# SynchronousBuck.net
KiCad netlist of a schematic drawn in Altium Designer
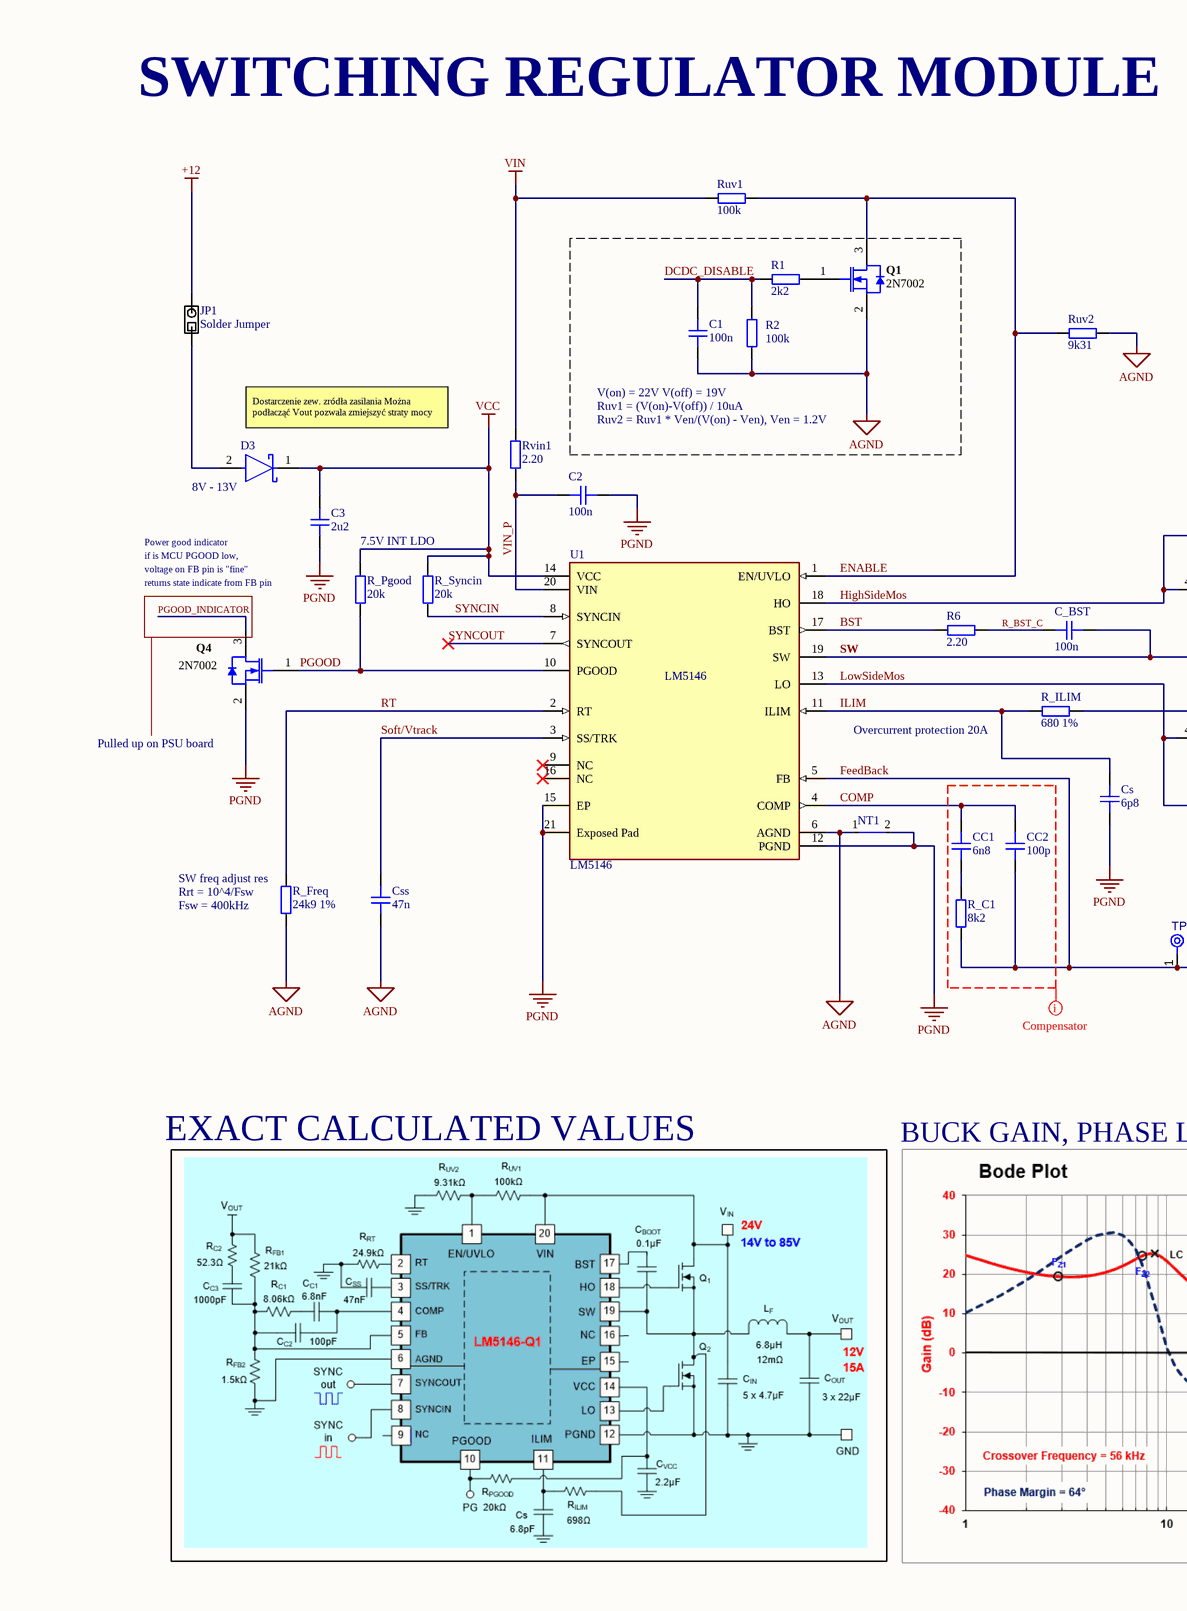
[diagram p0: SynchronousBuck.SchDoc, middle]
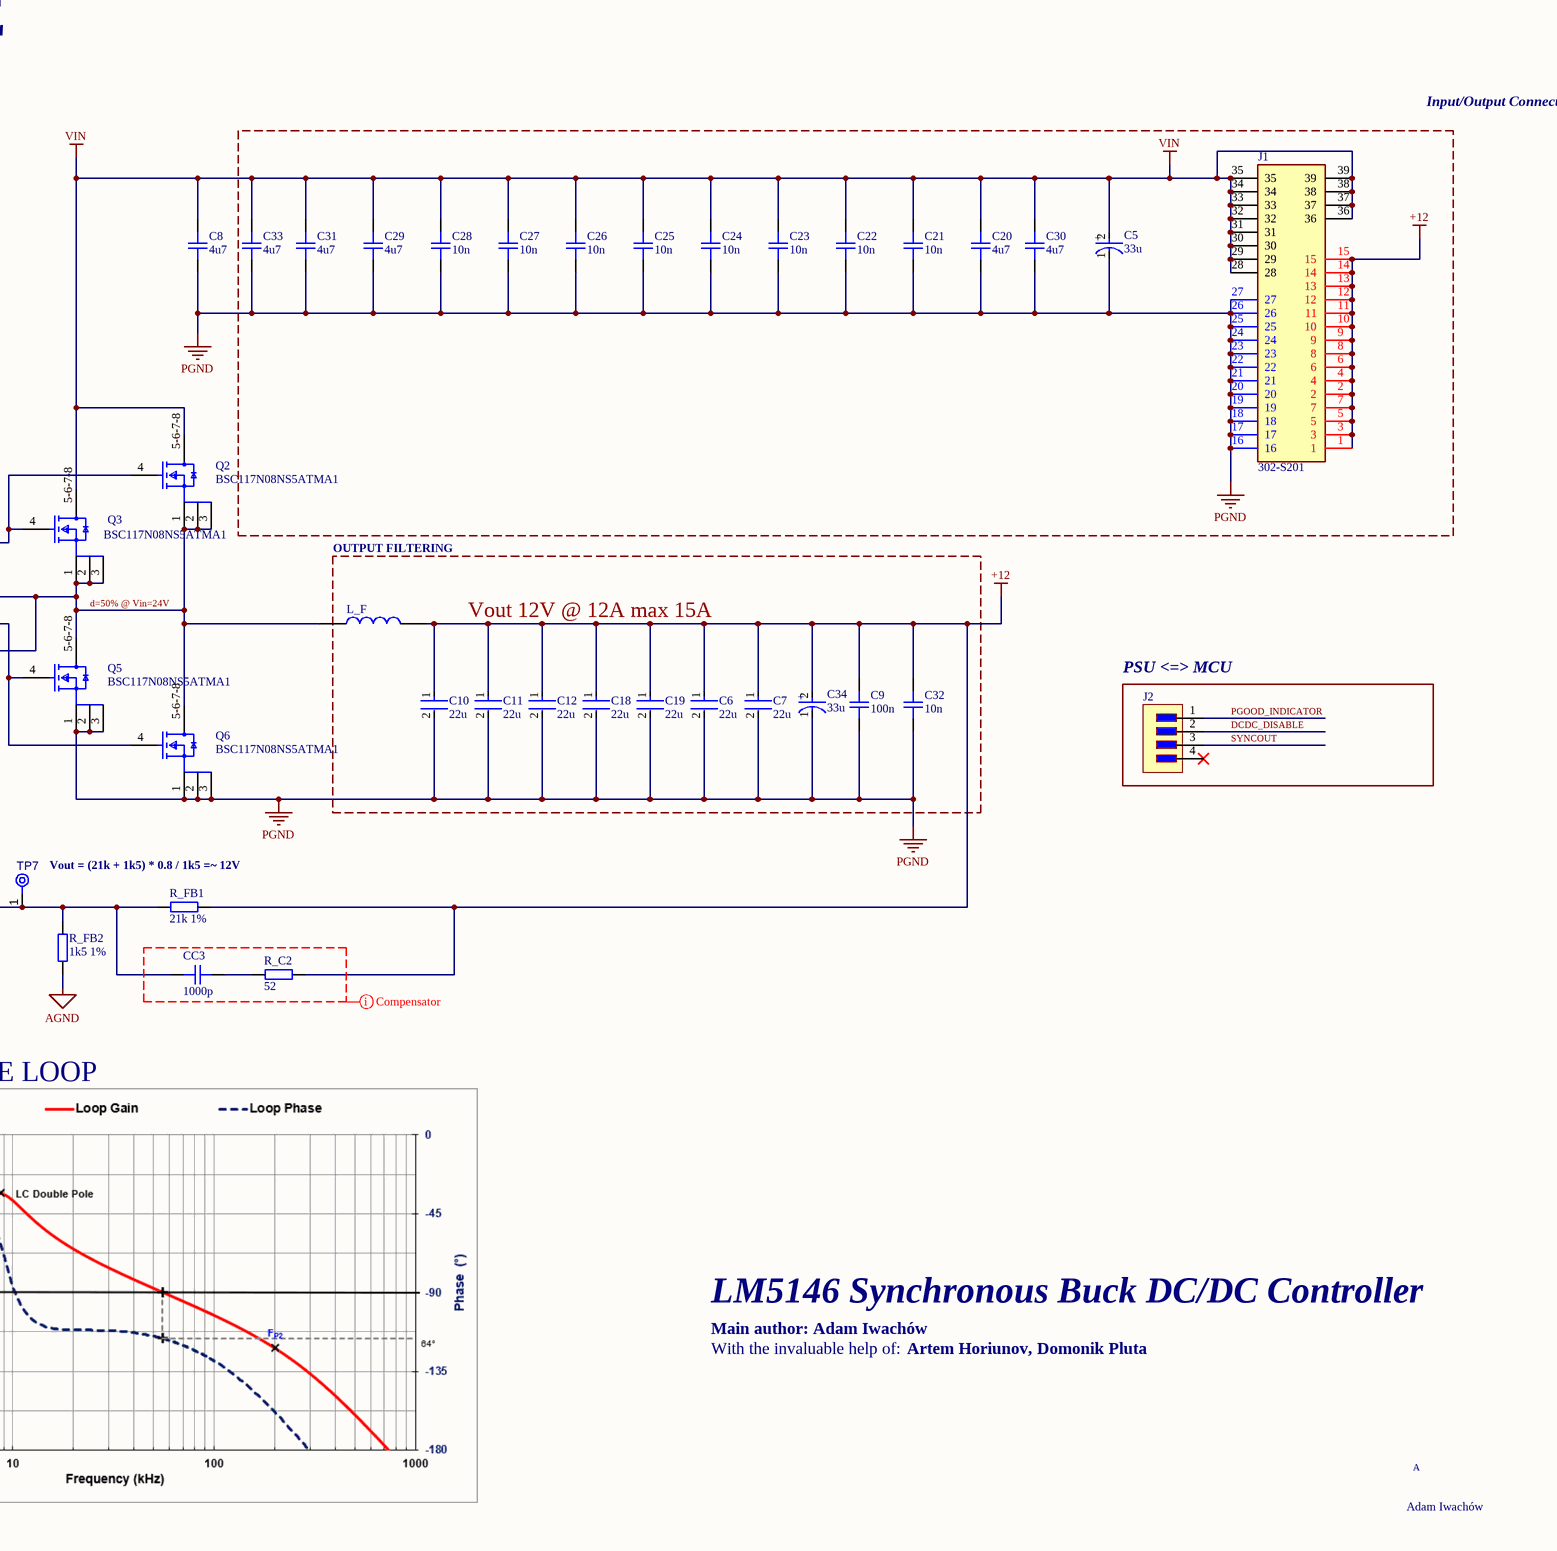
[diagram p1: SynchronousBuck.SchDoc, right]

(export (version "E")
  (design (tool "Eeschema 10.0.6"))
  (components
    (comp (ref "C1")
      (value "100n")
      (footprint "CAP_0603")
      (description "Capacitor SMD 0603")
      (libsource (lib "Schematic-Lib-PhilsLab") (part "CAP_0603"))
    )
    (comp (ref "C2")
      (value "100n")
      (footprint "CAP_0603")
      (description "Capacitor SMD 0603")
      (libsource (lib "Schematic-Lib-PhilsLab") (part "CAP_0603"))
    )
    (comp (ref "C3")
      (value "2u2")
      (footprint "CAP_0603")
      (description "Capacitor SMD 0603")
      (libsource (lib "Schematic-Lib-PhilsLab") (part "CAP_0603"))
    )
    (comp (ref "C5")
      (value "33u")
      (footprint "FP-FKG-MFG")
      (description "CAP ALUM 220UF 20% 50V SMD EEE-FK1H221GP")
      (fields (field (name "VOLTAGE") "50V") (field (name "TOLERANCE") "20%"))
      (libsource (lib "Altium Content Vault") (part "a00bbbee19879c290e62620ae7e47b1"))
    )
    (comp (ref "C6")
      (value "22u")
      (footprint "FP-GRM32E-0_3-0_2-MFG")
      (fields (field (name "VOLTAGE") "25V") (field (name "TOLERANCE") "10%"))
      (libsource (lib "Altium Content Vault") (part "02cd4be3c70576c341d710602a673aa"))
    )
    (comp (ref "C7")
      (value "22u")
      (footprint "FP-GRM32E-0_3-0_2-MFG")
      (fields (field (name "VOLTAGE") "25V") (field (name "TOLERANCE") "10%"))
      (libsource (lib "Altium Content Vault") (part "02cd4be3c70576c341d710602a673aa"))
    )
    (comp (ref "C8")
      (value "4u7")
      (footprint "CAP_1210")
      (description "Capacitor SMD 1210")
      (libsource (lib "Schematic-Lib-PhilsLab") (part "CAP_1210"))
    )
    (comp (ref "C9")
      (value "100n")
      (footprint "CAP_0603")
      (description "Capacitor SMD 0603")
      (libsource (lib "Schematic-Lib-PhilsLab") (part "CAP_0603"))
    )
    (comp (ref "C10")
      (value "22u")
      (footprint "FP-GRM32E-0_3-0_2-MFG")
      (fields (field (name "VOLTAGE") "25V") (field (name "TOLERANCE") "10%"))
      (libsource (lib "Altium Content Vault") (part "02cd4be3c70576c341d710602a673aa"))
    )
    (comp (ref "C11")
      (value "22u")
      (footprint "FP-GRM32E-0_3-0_2-MFG")
      (fields (field (name "VOLTAGE") "25V") (field (name "TOLERANCE") "10%"))
      (libsource (lib "Altium Content Vault") (part "02cd4be3c70576c341d710602a673aa"))
    )
    (comp (ref "C12")
      (value "22u")
      (footprint "FP-GRM32E-0_3-0_2-MFG")
      (fields (field (name "VOLTAGE") "25V") (field (name "TOLERANCE") "10%"))
      (libsource (lib "Altium Content Vault") (part "02cd4be3c70576c341d710602a673aa"))
    )
    (comp (ref "C18")
      (value "22u")
      (footprint "FP-GRM32E-0_3-0_2-MFG")
      (fields (field (name "VOLTAGE") "25V") (field (name "TOLERANCE") "10%"))
      (libsource (lib "Altium Content Vault") (part "02cd4be3c70576c341d710602a673aa"))
    )
    (comp (ref "C19")
      (value "22u")
      (footprint "FP-GRM32E-0_3-0_2-MFG")
      (fields (field (name "VOLTAGE") "25V") (field (name "TOLERANCE") "10%"))
      (libsource (lib "Altium Content Vault") (part "02cd4be3c70576c341d710602a673aa"))
    )
    (comp (ref "C20")
      (value "4u7")
      (footprint "CAP_1210")
      (description "Capacitor SMD 1210")
      (libsource (lib "Schematic-Lib-PhilsLab") (part "CAP_1210"))
    )
    (comp (ref "C21")
      (value "10n")
      (footprint "CAP_0603")
      (description "Capacitor SMD 0603")
      (libsource (lib "Schematic-Lib-PhilsLab") (part "CAP_0603"))
    )
    (comp (ref "C22")
      (value "10n")
      (footprint "CAP_0603")
      (description "Capacitor SMD 0603")
      (libsource (lib "Schematic-Lib-PhilsLab") (part "CAP_0603"))
    )
    (comp (ref "C23")
      (value "10n")
      (footprint "CAP_0603")
      (description "Capacitor SMD 0603")
      (libsource (lib "Schematic-Lib-PhilsLab") (part "CAP_0603"))
    )
    (comp (ref "C24")
      (value "10n")
      (footprint "CAP_0603")
      (description "Capacitor SMD 0603 GRM188R71H103KA01D")
      (libsource (lib "Schematic-Lib-PhilsLab") (part "CAP_0603"))
    )
    (comp (ref "C25")
      (value "10n")
      (footprint "CAP_0603")
      (description "Capacitor SMD 0603")
      (libsource (lib "Schematic-Lib-PhilsLab") (part "CAP_0603"))
    )
    (comp (ref "C26")
      (value "10n")
      (footprint "CAP_0603")
      (description "Capacitor SMD 0603")
      (libsource (lib "Schematic-Lib-PhilsLab") (part "CAP_0603"))
    )
    (comp (ref "C27")
      (value "10n")
      (footprint "CAP_0603")
      (description "Capacitor SMD 0603")
      (libsource (lib "Schematic-Lib-PhilsLab") (part "CAP_0603"))
    )
    (comp (ref "C28")
      (value "10n")
      (footprint "CAP_0603")
      (description "Capacitor SMD 0603")
      (libsource (lib "Schematic-Lib-PhilsLab") (part "CAP_0603"))
    )
    (comp (ref "C29")
      (value "4u7")
      (footprint "CAP_1210")
      (description "Capacitor SMD 1210")
      (libsource (lib "Schematic-Lib-PhilsLab") (part "CAP_1210"))
    )
    (comp (ref "C30")
      (value "4u7")
      (footprint "CAP_1210")
      (description "Capacitor SMD 1210")
      (libsource (lib "Schematic-Lib-PhilsLab") (part "CAP_1210"))
    )
    (comp (ref "C31")
      (value "4u7")
      (footprint "CAP_1210")
      (description "Capacitor SMD 1210")
      (libsource (lib "Schematic-Lib-PhilsLab") (part "CAP_1210"))
    )
    (comp (ref "C32")
      (value "10n")
      (footprint "CAP_0603")
      (description "Capacitor SMD 0603")
      (libsource (lib "Schematic-Lib-PhilsLab") (part "CAP_0603"))
    )
    (comp (ref "C33")
      (value "4u7")
      (footprint "CAP_1210")
      (description "Capacitor SMD 1210")
      (libsource (lib "Schematic-Lib-PhilsLab") (part "CAP_1210"))
    )
    (comp (ref "C34")
      (value "33u")
      (footprint "FP-FKG-MFG")
      (description "CAP ALUM 220UF 20% 50V SMD EEE-FK1H221GP")
      (fields (field (name "VOLTAGE") "50V") (field (name "TOLERANCE") "20%"))
      (libsource (lib "Altium Content Vault") (part "a00bbbee19879c290e62620ae7e47b1"))
    )
    (comp (ref "CC1")
      (value "6n8")
      (footprint "CAP_0603")
      (description "Capacitor SMD 0603")
      (libsource (lib "Schematic-Lib-PhilsLab") (part "CAP_0603"))
    )
    (comp (ref "CC2")
      (value "100p")
      (footprint "CAP_0603")
      (description "Capacitor SMD 0603")
      (libsource (lib "Schematic-Lib-PhilsLab") (part "CAP_0603"))
    )
    (comp (ref "CC3")
      (value "1000p")
      (footprint "CAP_0603")
      (description "Capacitor SMD 0603")
      (libsource (lib "Schematic-Lib-PhilsLab") (part "CAP_0603"))
    )
    (comp (ref "Cs")
      (value "6p8")
      (footprint "CAP_0603")
      (description "Capacitor SMD 0603")
      (libsource (lib "Schematic-Lib-PhilsLab") (part "CAP_0603"))
    )
    (comp (ref "Css")
      (value "47n")
      (footprint "CAP_0603")
      (description "Capacitor SMD 0603")
      (libsource (lib "Schematic-Lib-PhilsLab") (part "CAP_0603"))
    )
    (comp (ref "C_BST")
      (value "100n")
      (footprint "CAP_0603")
      (description "Capacitor SMD 0603")
      (libsource (lib "Schematic-Lib-PhilsLab") (part "CAP_0603"))
    )
    (comp (ref "D3")
      (value "BAT41KFILM")
      (footprint "FP-SOD-523-MFG")
      (description "DIODE SCHOTTKY 100V 200MA SOD523")
      (fields
        (field (name "OCTOPART") "https://octopart.com/bat41kfilm-stmicroelectronics-658186")
        (field (name "MANUFACTURER") "STMicroelectronics")
      )
      (libsource (lib "Altium Content Vault") (part "1d6ec82d83fb6aee721767c19dac4b9"))
    )
    (comp (ref "J1")
      (value "302-S201")
      (footprint "SHDR20W66P254_2X10_3300X905X905P")
      (description "Conn Shrouded Header HDR 20 POS 2.54mm Solder ST Thru-Hole")
      (libsource (lib "DCDCLIB") (part "DCDC_INPUT_CONN"))
    )
    (comp (ref "J2")
      (value "JST_XH_9PIN_254")
      (footprint "JST_XH_9PIN_254")
      (libsource (lib "DCDCLIB") (part "JST_XH_9PIN_254"))
    )
    (comp (ref "JP1")
      (value "Solder Jumper")
      (footprint "SolderJumper_Single")
      (description "Solder Jumper Single 0.5mm Pitch")
      (libsource (lib "Schematic-Lib-PhilsLab") (part "SolderJumper_Single"))
    )
    (comp (ref "L_F")
      (value "FEXL1510A-100M")
      (footprint "FEXL1510A-100M")
      (description "Wire Wound Moulded SMD Power Inductor")
      (fields (field (name "MANUFACTURER_PART_NUMBER") "FXL1360-4R7-M"))
      (libsource (lib "DCDCLIB") (part "FEXL1510A-100M"))
    )
    (comp (ref "NT1")
      (value "NT")
      (footprint "Netie")
      (description "Single point connection between nets")
      (libsource (lib "DCDCLIB") (part "NetTie"))
    )
    (comp (ref "Q1")
      (value "2N7002")
      (footprint "INF-PG-SOT23_M")
      (fields (field (name "MANUFACTURER") "Infineon"))
      (libsource (lib "Altium Content Vault") (part "INF-NDMOS-GSD-3"))
    )
    (comp (ref "Q2")
      (value "BSC117N08NS5ATMA1")
      (footprint "FP-PG-TDSON-8-MFG")
      (description "MOSFET N-CH 80V 49A 8TDSON")
      (fields
        (field (name "OCTOPART") "https://octopart.com/bsc117n08ns5atma1-infineon-52825716")
        (field (name "MANUFACTURER") "Infineon")
      )
      (libsource (lib "Altium Content Vault") (part "95ca5d46c4c8fe7d84c4fb5e2abfe3c"))
    )
    (comp (ref "Q3")
      (value "BSC117N08NS5ATMA1")
      (footprint "FP-PG-TDSON-8-MFG")
      (description "MOSFET N-CH 80V 49A 8TDSON")
      (fields
        (field (name "OCTOPART") "https://octopart.com/bsc117n08ns5atma1-infineon-52825716")
        (field (name "MANUFACTURER") "Infineon")
      )
      (libsource (lib "Altium Content Vault") (part "95ca5d46c4c8fe7d84c4fb5e2abfe3c"))
    )
    (comp (ref "Q4")
      (value "2N7002")
      (footprint "INF-PG-SOT23_M")
      (fields (field (name "MANUFACTURER") "Infineon"))
      (libsource (lib "Altium Content Vault") (part "INF-NDMOS-GSD-3"))
    )
    (comp (ref "Q5")
      (value "BSC117N08NS5ATMA1")
      (footprint "FP-PG-TDSON-8-MFG")
      (description "MOSFET N-CH 80V 49A 8TDSON")
      (fields
        (field (name "OCTOPART") "https://octopart.com/bsc117n08ns5atma1-infineon-52825716")
        (field (name "MANUFACTURER") "Infineon")
      )
      (libsource (lib "Altium Content Vault") (part "95ca5d46c4c8fe7d84c4fb5e2abfe3c"))
    )
    (comp (ref "Q6")
      (value "BSC117N08NS5ATMA1")
      (footprint "FP-PG-TDSON-8-MFG")
      (description "MOSFET N-CH 80V 49A 8TDSON")
      (fields
        (field (name "OCTOPART") "https://octopart.com/bsc117n08ns5atma1-infineon-52825716")
        (field (name "MANUFACTURER") "Infineon")
      )
      (libsource (lib "Altium Content Vault") (part "95ca5d46c4c8fe7d84c4fb5e2abfe3c"))
    )
    (comp (ref "R1")
      (value "2k2")
      (footprint "RES_0603")
      (description "Resistor SMD 0603")
      (libsource (lib "Schematic-Lib-PhilsLab") (part "RES_0603"))
    )
    (comp (ref "R2")
      (value "100k")
      (footprint "RES_0603")
      (description "Resistor SMD 0603")
      (libsource (lib "Schematic-Lib-PhilsLab") (part "RES_0603"))
    )
    (comp (ref "R6")
      (value "2.20")
      (footprint "RES_0603")
      (description "Resistor SMD 0603")
      (libsource (lib "Schematic-Lib-PhilsLab") (part "RES_0603"))
    )
    (comp (ref "Ruv1")
      (value "100k")
      (footprint "RES_0603")
      (description "Resistor SMD 0603")
      (libsource (lib "Schematic-Lib-PhilsLab") (part "RES_0603"))
    )
    (comp (ref "Ruv2")
      (value "9k31")
      (footprint "RES_0603")
      (description "Resistor SMD 0603")
      (libsource (lib "Schematic-Lib-PhilsLab") (part "RES_0603"))
    )
    (comp (ref "Rvin1")
      (value "2.20")
      (footprint "RES_0603")
      (description "Resistor SMD 0603")
      (libsource (lib "Schematic-Lib-PhilsLab") (part "RES_0603"))
    )
    (comp (ref "R_C1")
      (value "8k2")
      (footprint "RES_0603")
      (description "Resistor SMD 0603")
      (libsource (lib "Schematic-Lib-PhilsLab") (part "RES_0603"))
    )
    (comp (ref "R_C2")
      (value "52")
      (footprint "RES_0603")
      (description "Resistor SMD 0603")
      (libsource (lib "Schematic-Lib-PhilsLab") (part "RES_0603"))
    )
    (comp (ref "R_FB1")
      (value "21k 1%")
      (footprint "RES_0603")
      (description "Resistor SMD 0603")
      (libsource (lib "Schematic-Lib-PhilsLab") (part "RES_0603"))
    )
    (comp (ref "R_FB2")
      (value "1k5 1%")
      (footprint "RES_0603")
      (description "Resistor SMD 0603")
      (libsource (lib "Schematic-Lib-PhilsLab") (part "RES_0603"))
    )
    (comp (ref "R_Freq")
      (value "24k9 1%")
      (footprint "RES_0603")
      (description "Resistor SMD 0603")
      (libsource (lib "Schematic-Lib-PhilsLab") (part "RES_0603"))
    )
    (comp (ref "R_ILIM")
      (value "680 1%")
      (footprint "RES_0603")
      (description "Resistor SMD 0603")
      (libsource (lib "Schematic-Lib-PhilsLab") (part "RES_0603"))
    )
    (comp (ref "R_Pgood")
      (value "20k")
      (footprint "RES_0603")
      (description "Resistor SMD 0603")
      (libsource (lib "Schematic-Lib-PhilsLab") (part "RES_0603"))
    )
    (comp (ref "R_Syncin")
      (value "20k")
      (footprint "RES_0603")
      (description "Resistor SMD 0603")
      (libsource (lib "Schematic-Lib-PhilsLab") (part "RES_0603"))
    )
    (comp (ref "TP7")
      (value "TPAD6R")
      (footprint "TP06R")
      (description "0.6mm round")
      (libsource (lib "Wroclaw University of Technology") (part "CMP-001-0001-4"))
    )
    (comp (ref "U1")
      (value "LM5146")
      (footprint "LM5146RGYR")
      (libsource (lib "Schematic-Lib-PhilsLab") (part "LM5146"))
    )
  )
  (nets
    (net (code "1") (name "+12") (class "Default")
      (node (ref "C10") (pin "1") (pinfunction "1_1") (pintype "passive"))
      (node (ref "C11") (pin "1") (pinfunction "1_1") (pintype "passive"))
      (node (ref "C12") (pin "1") (pinfunction "1_1") (pintype "passive"))
      (node (ref "C18") (pin "1") (pinfunction "1_1") (pintype "passive"))
      (node (ref "C19") (pin "1") (pinfunction "1_1") (pintype "passive"))
      (node (ref "C32") (pin "2") (pinfunction "2_2") (pintype "passive"))
      (node (ref "C34") (pin "2") (pinfunction "A_2") (pintype "passive"))
      (node (ref "C6") (pin "1") (pinfunction "1_1") (pintype "passive"))
      (node (ref "C7") (pin "1") (pinfunction "1_1") (pintype "passive"))
      (node (ref "C9") (pin "2") (pinfunction "2_2") (pintype "passive"))
      (node (ref "J1") (pin "1") (pinfunction "1_1") (pintype "passive"))
      (node (ref "J1") (pin "10") (pinfunction "10_10") (pintype "passive"))
      (node (ref "J1") (pin "11") (pinfunction "11_11") (pintype "passive"))
      (node (ref "J1") (pin "12") (pinfunction "12_12") (pintype "passive"))
      (node (ref "J1") (pin "13") (pinfunction "13_13") (pintype "passive"))
      (node (ref "J1") (pin "14") (pinfunction "14_14") (pintype "passive"))
      (node (ref "J1") (pin "15") (pinfunction "15_15") (pintype "passive"))
      (node (ref "J1") (pin "2") (pinfunction "2_2") (pintype "passive"))
      (node (ref "J1") (pin "3") (pinfunction "3_3") (pintype "passive"))
      (node (ref "J1") (pin "4") (pinfunction "4_4") (pintype "passive"))
      (node (ref "J1") (pin "5") (pinfunction "5_5") (pintype "passive"))
      (node (ref "J1") (pin "6") (pinfunction "6_6") (pintype "passive"))
      (node (ref "J1") (pin "7") (pinfunction "7_7") (pintype "passive"))
      (node (ref "J1") (pin "8") (pinfunction "8_8") (pintype "passive"))
      (node (ref "J1") (pin "9") (pinfunction "9_9") (pintype "passive"))
      (node (ref "JP1") (pin "2") (pinfunction "2_2") (pintype "passive"))
      (node (ref "L_F") (pin "2") (pinfunction "2_2") (pintype "passive"))
      (node (ref "R_C2") (pin "1") (pinfunction "1_1") (pintype "passive"))
      (node (ref "R_FB1") (pin "1") (pinfunction "1_1") (pintype "passive"))
    )
    (net (code "3") (name "/BST") (class "Default")
      (node (ref "R6") (pin "1") (pinfunction "1_1") (pintype "passive"))
      (node (ref "U1") (pin "17") (pinfunction "BST_17") (pintype "output"))
    )
    (net (code "4") (name "/COMP") (class "Default")
      (node (ref "CC1") (pin "2") (pinfunction "2_2") (pintype "passive"))
      (node (ref "CC2") (pin "2") (pinfunction "2_2") (pintype "passive"))
      (node (ref "U1") (pin "4") (pinfunction "COMP_4") (pintype "output"))
    )
    (net (code "5") (name "/DCDC_DISABLE") (class "Default")
      (node (ref "C1") (pin "2") (pinfunction "2_2") (pintype "passive"))
      (node (ref "J2") (pin "2") (pintype "passive"))
      (node (ref "R1") (pin "1") (pinfunction "1_1") (pintype "passive"))
      (node (ref "R2") (pin "2") (pinfunction "2_2") (pintype "passive"))
    )
    (net (code "6") (name "/ENABLE") (class "Default")
      (node (ref "Q1") (pin "3") (pinfunction "DRAIN_3") (pintype "passive"))
      (node (ref "Ruv1") (pin "1") (pinfunction "1_1") (pintype "passive"))
      (node (ref "Ruv2") (pin "2") (pinfunction "2_2") (pintype "passive"))
      (node (ref "U1") (pin "1") (pinfunction "EN/UVLO_1") (pintype "input"))
    )
    (net (code "7") (name "/FeedBack") (class "Default")
      (node (ref "CC2") (pin "1") (pinfunction "1_1") (pintype "passive"))
      (node (ref "CC3") (pin "2") (pinfunction "2_2") (pintype "passive"))
      (node (ref "R_C1") (pin "1") (pinfunction "1_1") (pintype "passive"))
      (node (ref "R_FB1") (pin "2") (pinfunction "2_2") (pintype "passive"))
      (node (ref "R_FB2") (pin "2") (pinfunction "2_2") (pintype "passive"))
      (node (ref "TP7") (pin "1") (pinfunction "TP_1") (pintype "passive"))
      (node (ref "U1") (pin "5") (pinfunction "FB_5") (pintype "input"))
    )
    (net (code "8") (name "/HighSideMos") (class "Default")
      (node (ref "Q2") (pin "4") (pinfunction "G_4") (pintype "passive"))
      (node (ref "Q3") (pin "4") (pinfunction "G_4") (pintype "passive"))
      (node (ref "U1") (pin "18") (pinfunction "HO_18") (pintype "power_in"))
    )
    (net (code "9") (name "/ILIM") (class "Default")
      (node (ref "Cs") (pin "2") (pinfunction "2_2") (pintype "passive"))
      (node (ref "R_ILIM") (pin "1") (pinfunction "1_1") (pintype "passive"))
      (node (ref "U1") (pin "11") (pinfunction "ILIM_11") (pintype "input"))
    )
    (net (code "10") (name "/LowSideMos") (class "Default")
      (node (ref "Q5") (pin "4") (pinfunction "G_4") (pintype "passive"))
      (node (ref "Q6") (pin "4") (pinfunction "G_4") (pintype "passive"))
      (node (ref "U1") (pin "13") (pinfunction "LO_13") (pintype "power_in"))
    )
    (net (code "11") (name "/PGOOD") (class "Default")
      (node (ref "Q4") (pin "1") (pinfunction "GATE_1") (pintype "passive"))
      (node (ref "R_Pgood") (pin "2") (pinfunction "2_2") (pintype "passive"))
      (node (ref "U1") (pin "10") (pinfunction "PGOOD_10") (pintype "open_collector"))
    )
    (net (code "12") (name "/PGOOD_INDICATOR") (class "Default")
      (node (ref "J2") (pin "1") (pintype "passive"))
      (node (ref "Q4") (pin "3") (pinfunction "DRAIN_3") (pintype "passive"))
    )
    (net (code "13") (name "/RT") (class "Default")
      (node (ref "R_Freq") (pin "2") (pinfunction "2_2") (pintype "passive"))
      (node (ref "U1") (pin "2") (pinfunction "RT_2") (pintype "input"))
    )
    (net (code "14") (name "/R_BST_C") (class "Default")
      (node (ref "C_BST") (pin "1") (pinfunction "1_1") (pintype "passive"))
      (node (ref "R6") (pin "2") (pinfunction "2_2") (pintype "passive"))
    )
    (net (code "15") (name "/SW") (class "Default")
      (node (ref "C_BST") (pin "2") (pinfunction "2_2") (pintype "passive"))
      (node (ref "L_F") (pin "1") (pinfunction "1_1") (pintype "passive"))
      (node (ref "Q2") (pin "1") (pinfunction "S_1") (pintype "passive"))
      (node (ref "Q2") (pin "2") (pinfunction "S_2") (pintype "passive"))
      (node (ref "Q2") (pin "3") (pinfunction "S_3") (pintype "passive"))
      (node (ref "Q3") (pin "1") (pinfunction "S_1") (pintype "passive"))
      (node (ref "Q3") (pin "2") (pinfunction "S_2") (pintype "passive"))
      (node (ref "Q3") (pin "3") (pinfunction "S_3") (pintype "passive"))
      (node (ref "Q5") (pin "5-6-7-8") (pinfunction "D_5-6-7-8") (pintype "passive"))
      (node (ref "Q6") (pin "5-6-7-8") (pinfunction "D_5-6-7-8") (pintype "passive"))
      (node (ref "R_ILIM") (pin "2") (pinfunction "2_2") (pintype "passive"))
      (node (ref "U1") (pin "19") (pinfunction "SW_19") (pintype "power_in"))
    )
    (net (code "16") (name "/SYNCIN") (class "Default")
      (node (ref "R_Syncin") (pin "1") (pinfunction "1_1") (pintype "passive"))
      (node (ref "U1") (pin "8") (pinfunction "SYNCIN_8") (pintype "input"))
    )
    (net (code "17") (name "/SYNCOUT") (class "Default")
      (node (ref "J2") (pin "3") (pintype "passive"))
      (node (ref "U1") (pin "7") (pinfunction "SYNCOUT_7") (pintype "output"))
    )
    (net (code "18") (name "/Soft{slash}Vtrack") (class "Default")
      (node (ref "Css") (pin "2") (pinfunction "2_2") (pintype "passive"))
      (node (ref "U1") (pin "3") (pinfunction "SS/TRK_3") (pintype "input"))
    )
    (net (code "19") (name "/VIN_P") (class "Default")
      (node (ref "C2") (pin "1") (pinfunction "1_1") (pintype "passive"))
      (node (ref "Rvin1") (pin "1") (pinfunction "1_1") (pintype "passive"))
      (node (ref "U1") (pin "20") (pinfunction "VIN_20") (pintype "power_in"))
    )
    (net (code "20") (name "AGND") (class "Default")
      (node (ref "C1") (pin "1") (pinfunction "1_1") (pintype "passive"))
      (node (ref "Css") (pin "1") (pinfunction "1_1") (pintype "passive"))
      (node (ref "NT1") (pin "1") (pinfunction "1_1") (pintype "passive"))
      (node (ref "Q1") (pin "2") (pinfunction "SOURCE_2") (pintype "passive"))
      (node (ref "R2") (pin "1") (pinfunction "1_1") (pintype "passive"))
      (node (ref "R_FB2") (pin "1") (pinfunction "1_1") (pintype "passive"))
      (node (ref "R_Freq") (pin "1") (pinfunction "1_1") (pintype "passive"))
      (node (ref "Ruv2") (pin "1") (pinfunction "1_1") (pintype "passive"))
      (node (ref "U1") (pin "6") (pinfunction "AGND_6") (pintype "power_in"))
    )
    (net (code "21") (name "Net-(CC1-Pad1)") (class "Default")
      (node (ref "CC1") (pin "1") (pinfunction "1_1") (pintype "passive"))
      (node (ref "R_C1") (pin "2") (pinfunction "2_2") (pintype "passive"))
    )
    (net (code "22") (name "Net-(CC3-Pad1)") (class "Default")
      (node (ref "CC3") (pin "1") (pinfunction "1_1") (pintype "passive"))
      (node (ref "R_C2") (pin "2") (pinfunction "2_2") (pintype "passive"))
    )
    (net (code "23") (name "Net-(D3-A)") (class "Default")
      (node (ref "D3") (pin "2") (pinfunction "A_2") (pintype "passive"))
      (node (ref "JP1") (pin "1") (pinfunction "1_1") (pintype "passive"))
    )
    (net (code "24") (name "Net-(Q1-GATE)") (class "Default")
      (node (ref "Q1") (pin "1") (pinfunction "GATE_1") (pintype "passive"))
      (node (ref "R1") (pin "2") (pinfunction "2_2") (pintype "passive"))
    )
    (net (code "25") (name "PGND") (class "Default")
      (node (ref "C10") (pin "2") (pinfunction "2_2") (pintype "passive"))
      (node (ref "C11") (pin "2") (pinfunction "2_2") (pintype "passive"))
      (node (ref "C12") (pin "2") (pinfunction "2_2") (pintype "passive"))
      (node (ref "C18") (pin "2") (pinfunction "2_2") (pintype "passive"))
      (node (ref "C19") (pin "2") (pinfunction "2_2") (pintype "passive"))
      (node (ref "C2") (pin "2") (pinfunction "2_2") (pintype "passive"))
      (node (ref "C20") (pin "1") (pinfunction "1_1") (pintype "passive"))
      (node (ref "C21") (pin "1") (pinfunction "1_1") (pintype "passive"))
      (node (ref "C22") (pin "1") (pinfunction "1_1") (pintype "passive"))
      (node (ref "C23") (pin "1") (pinfunction "1_1") (pintype "passive"))
      (node (ref "C24") (pin "1") (pinfunction "1_1") (pintype "passive"))
      (node (ref "C25") (pin "1") (pinfunction "1_1") (pintype "passive"))
      (node (ref "C26") (pin "1") (pinfunction "1_1") (pintype "passive"))
      (node (ref "C27") (pin "1") (pinfunction "1_1") (pintype "passive"))
      (node (ref "C28") (pin "1") (pinfunction "1_1") (pintype "passive"))
      (node (ref "C29") (pin "1") (pinfunction "1_1") (pintype "passive"))
      (node (ref "C3") (pin "1") (pinfunction "1_1") (pintype "passive"))
      (node (ref "C30") (pin "1") (pinfunction "1_1") (pintype "passive"))
      (node (ref "C31") (pin "1") (pinfunction "1_1") (pintype "passive"))
      (node (ref "C32") (pin "1") (pinfunction "1_1") (pintype "passive"))
      (node (ref "C33") (pin "1") (pinfunction "1_1") (pintype "passive"))
      (node (ref "C34") (pin "1") (pinfunction "C_1") (pintype "passive"))
      (node (ref "C5") (pin "1") (pinfunction "C_1") (pintype "passive"))
      (node (ref "C6") (pin "2") (pinfunction "2_2") (pintype "passive"))
      (node (ref "C7") (pin "2") (pinfunction "2_2") (pintype "passive"))
      (node (ref "C8") (pin "1") (pinfunction "1_1") (pintype "passive"))
      (node (ref "C9") (pin "1") (pinfunction "1_1") (pintype "passive"))
      (node (ref "Cs") (pin "1") (pinfunction "1_1") (pintype "passive"))
      (node (ref "J1") (pin "16") (pinfunction "16_16") (pintype "passive"))
      (node (ref "J1") (pin "17") (pinfunction "17_17") (pintype "passive"))
      (node (ref "J1") (pin "18") (pinfunction "18_18") (pintype "passive"))
      (node (ref "J1") (pin "19") (pinfunction "19_19") (pintype "passive"))
      (node (ref "J1") (pin "20") (pinfunction "20_20") (pintype "passive"))
      (node (ref "J1") (pin "21") (pinfunction "21_21") (pintype "passive"))
      (node (ref "J1") (pin "22") (pinfunction "22_22") (pintype "passive"))
      (node (ref "J1") (pin "23") (pinfunction "23_23") (pintype "passive"))
      (node (ref "J1") (pin "24") (pinfunction "24_24") (pintype "passive"))
      (node (ref "J1") (pin "25") (pinfunction "25_25") (pintype "passive"))
      (node (ref "J1") (pin "26") (pinfunction "26_26") (pintype "passive"))
      (node (ref "J1") (pin "27") (pinfunction "27_27") (pintype "passive"))
      (node (ref "NT1") (pin "2") (pinfunction "2_2") (pintype "passive"))
      (node (ref "Q4") (pin "2") (pinfunction "SOURCE_2") (pintype "passive"))
      (node (ref "Q5") (pin "1") (pinfunction "S_1") (pintype "passive"))
      (node (ref "Q5") (pin "2") (pinfunction "S_2") (pintype "passive"))
      (node (ref "Q5") (pin "3") (pinfunction "S_3") (pintype "passive"))
      (node (ref "Q6") (pin "1") (pinfunction "S_1") (pintype "passive"))
      (node (ref "Q6") (pin "2") (pinfunction "S_2") (pintype "passive"))
      (node (ref "Q6") (pin "3") (pinfunction "S_3") (pintype "passive"))
      (node (ref "U1") (pin "12") (pinfunction "PGND_12") (pintype "power_in"))
      (node (ref "U1") (pin "15") (pinfunction "EP_15") (pintype "power_in"))
      (node (ref "U1") (pin "21") (pinfunction "Exposed_Pad_21") (pintype "power_in"))
    )
    (net (code "26") (name "VCC") (class "Default")
      (node (ref "C3") (pin "2") (pinfunction "2_2") (pintype "passive"))
      (node (ref "D3") (pin "1") (pinfunction "C_1") (pintype "passive"))
      (node (ref "R_Pgood") (pin "1") (pinfunction "1_1") (pintype "passive"))
      (node (ref "R_Syncin") (pin "2") (pinfunction "2_2") (pintype "passive"))
      (node (ref "U1") (pin "14") (pinfunction "VCC_14") (pintype "power_in"))
    )
    (net (code "27") (name "VIN") (class "Default")
      (node (ref "C20") (pin "2") (pinfunction "2_2") (pintype "passive"))
      (node (ref "C21") (pin "2") (pinfunction "2_2") (pintype "passive"))
      (node (ref "C22") (pin "2") (pinfunction "2_2") (pintype "passive"))
      (node (ref "C23") (pin "2") (pinfunction "2_2") (pintype "passive"))
      (node (ref "C24") (pin "2") (pinfunction "2_2") (pintype "passive"))
      (node (ref "C25") (pin "2") (pinfunction "2_2") (pintype "passive"))
      (node (ref "C26") (pin "2") (pinfunction "2_2") (pintype "passive"))
      (node (ref "C27") (pin "2") (pinfunction "2_2") (pintype "passive"))
      (node (ref "C28") (pin "2") (pinfunction "2_2") (pintype "passive"))
      (node (ref "C29") (pin "2") (pinfunction "2_2") (pintype "passive"))
      (node (ref "C30") (pin "2") (pinfunction "2_2") (pintype "passive"))
      (node (ref "C31") (pin "2") (pinfunction "2_2") (pintype "passive"))
      (node (ref "C33") (pin "2") (pinfunction "2_2") (pintype "passive"))
      (node (ref "C5") (pin "2") (pinfunction "A_2") (pintype "passive"))
      (node (ref "C8") (pin "2") (pinfunction "2_2") (pintype "passive"))
      (node (ref "J1") (pin "28") (pinfunction "28_28") (pintype "passive"))
      (node (ref "J1") (pin "29") (pinfunction "29_29") (pintype "passive"))
      (node (ref "J1") (pin "30") (pinfunction "30_30") (pintype "passive"))
      (node (ref "J1") (pin "31") (pinfunction "31_31") (pintype "passive"))
      (node (ref "J1") (pin "32") (pinfunction "32_32") (pintype "passive"))
      (node (ref "J1") (pin "33") (pinfunction "33_33") (pintype "passive"))
      (node (ref "J1") (pin "34") (pinfunction "34_34") (pintype "passive"))
      (node (ref "J1") (pin "35") (pinfunction "35_35") (pintype "passive"))
      (node (ref "J1") (pin "36") (pinfunction "36_36") (pintype "passive"))
      (node (ref "J1") (pin "37") (pinfunction "37_37") (pintype "passive"))
      (node (ref "J1") (pin "38") (pinfunction "38_38") (pintype "passive"))
      (node (ref "J1") (pin "39") (pinfunction "39_39") (pintype "passive"))
      (node (ref "Q2") (pin "5-6-7-8") (pinfunction "D_5-6-7-8") (pintype "passive"))
      (node (ref "Q3") (pin "5-6-7-8") (pinfunction "D_5-6-7-8") (pintype "passive"))
      (node (ref "Ruv1") (pin "2") (pinfunction "2_2") (pintype "passive"))
      (node (ref "Rvin1") (pin "2") (pinfunction "2_2") (pintype "passive"))
    )
    (net (code "28") (name "unconnected-(J2-Pad4)") (class "Default")
      (node (ref "J2") (pin "4") (pintype "passive+no_connect"))
    )
    (net (code "29") (name "unconnected-(U1-NC-Pad9)") (class "Default")
      (node (ref "U1") (pin "9") (pinfunction "NC_9") (pintype "passive+no_connect"))
    )
    (net (code "30") (name "unconnected-(U1-NC-Pad16)") (class "Default")
      (node (ref "U1") (pin "16") (pinfunction "NC_16") (pintype "passive+no_connect"))
    )
  )
)
